# aspirin.net
KiCad netlist of a schematic drawn in EAGLE
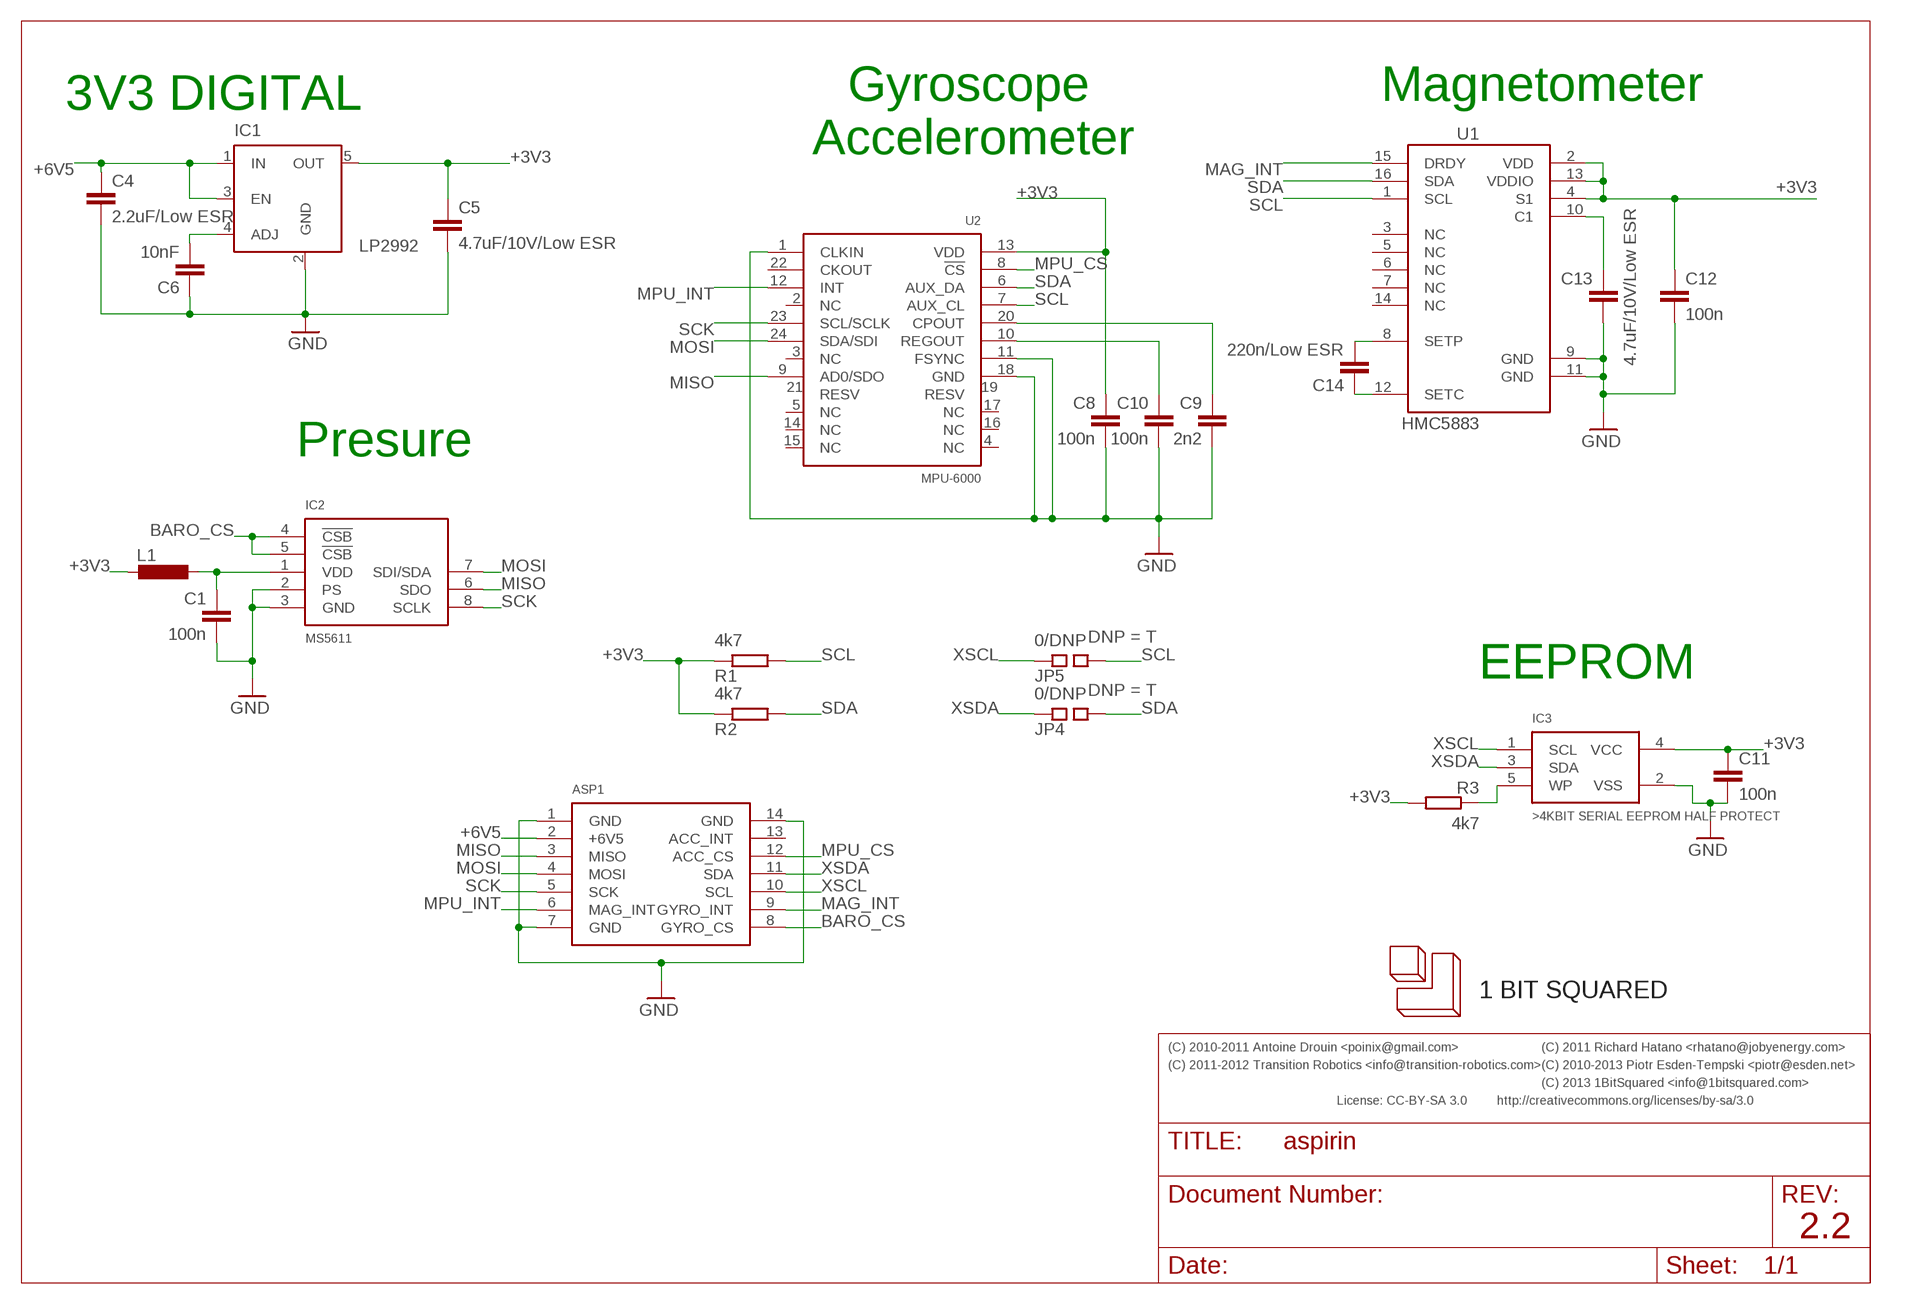
[diagram p0: schematic, sheet 1]

(export (version "E")
  (design (tool "Eeschema 10.0.6"))
  (components
    (comp (ref "ASP1")
      (value "ASPIRIN")
      (footprint "eagle-import:ASPIRIN_CASTELLATED")
      (fields (field (name "PARTNO") "pcb-aspirin"))
      (libsource (lib "eagle-import") (part "ASPIRIN"))
    )
    (comp (ref "C1")
      (value "100n")
      (footprint "eagle-import:0402-CAP")
      (fields (field (name "PARTNO") "cap-cer-0402-100n"))
      (libsource (lib "eagle-import") (part "CAPACITOR-0402"))
    )
    (comp (ref "C4")
      (value "2.2uF/Low ESR")
      (footprint "eagle-import:0603-CAP")
      (fields (field (name "PARTNO") "cap-cer-0603-2u2"))
      (libsource (lib "eagle-import") (part "CAPACITOR-0603"))
    )
    (comp (ref "C5")
      (value "4.7uF/10V/Low ESR")
      (footprint "eagle-import:0603-CAP")
      (fields (field (name "PARTNO") "cap-cer-0603-4u7"))
      (libsource (lib "eagle-import") (part "CAPACITOR-0603"))
    )
    (comp (ref "C6")
      (value "10nF")
      (footprint "eagle-import:0402-CAP")
      (fields (field (name "PARTNO") "cap-cer-0402-10n"))
      (libsource (lib "eagle-import") (part "CAPACITOR-0402"))
    )
    (comp (ref "C8")
      (value "100n")
      (footprint "eagle-import:0402-CAP")
      (fields (field (name "PARTNO") "cap-cer-0402-100n"))
      (libsource (lib "eagle-import") (part "CAPACITOR-0402"))
    )
    (comp (ref "C9")
      (value "2n2")
      (footprint "eagle-import:0402-CAP")
      (fields (field (name "PARTNO") "cap-cer-0402-2n2"))
      (libsource (lib "eagle-import") (part "CAPACITOR-0402"))
    )
    (comp (ref "C10")
      (value "100n")
      (footprint "eagle-import:0402-CAP")
      (fields (field (name "PARTNO") "cap-cer-0402-100n"))
      (libsource (lib "eagle-import") (part "CAPACITOR-0402"))
    )
    (comp (ref "C11")
      (value "100n")
      (footprint "eagle-import:0402-CAP")
      (fields (field (name "PARTNO") "cap-cer-0402-100n"))
      (libsource (lib "eagle-import") (part "CAPACITOR-0402"))
    )
    (comp (ref "C12")
      (value "100n")
      (footprint "eagle-import:0402-CAP")
      (fields (field (name "PARTNO") "cap-cer-0402-100n"))
      (libsource (lib "eagle-import") (part "CAPACITOR-0402"))
    )
    (comp (ref "C13")
      (value "4.7uF/10V/Low ESR")
      (footprint "eagle-import:0603-CAP")
      (fields (field (name "PARTNO") "cap-cer-0603-4u7"))
      (libsource (lib "eagle-import") (part "CAPACITOR-0603"))
    )
    (comp (ref "C14")
      (value "220n/Low ESR")
      (footprint "eagle-import:0603-CAP")
      (fields (field (name "PARTNO") "cap-cer-0603-220n"))
      (libsource (lib "eagle-import") (part "CAPACITOR-0603"))
    )
    (comp (ref "IC1")
      (value "LP2992")
      (footprint "eagle-import:SOT23-5")
      (fields (field (name "PARTNO") "vreg-sot-23-5-3v3"))
      (libsource (lib "eagle-import") (part "MIC5219BM5"))
    )
    (comp (ref "IC2")
      (value "MS5611")
      (footprint "eagle-import:QFN-MS5611")
      (fields (field (name "PARTNO") "sensr-qfn-8-baro"))
      (libsource (lib "eagle-import") (part "MS5611"))
    )
    (comp (ref "IC3")
      (value ">4KBIT SERIAL EEPROM HALF PROTECT")
      (footprint "eagle-import:SOT23-5")
      (fields (field (name "PARTNO") "ic-sot-23-5-4k-eeprom"))
      (libsource (lib "eagle-import") (part "I2C_EEPROM-SOT23-5"))
    )
    (comp (ref "JP4")
      (value "0/DNP")
      (footprint "eagle-import:0402-SQJMP")
      (fields (field (name "DNP") "T") (field (name "PARTNO") "res-0402-0"))
      (libsource (lib "eagle-import") (part "SQ_JMP-0402"))
    )
    (comp (ref "JP5")
      (value "0/DNP")
      (footprint "eagle-import:0402-SQJMP")
      (fields (field (name "DNP") "T") (field (name "PARTNO") "res-0402-0"))
      (libsource (lib "eagle-import") (part "SQ_JMP-0402"))
    )
    (comp (ref "L1")
      (value "INDUCTOR-0603")
      (footprint "eagle-import:0603-IND")
      (fields (field (name "PARTNO") "ferrite-0603-600ohm"))
      (libsource (lib "eagle-import") (part "INDUCTOR-0603"))
    )
    (comp (ref "R1")
      (value "4k7")
      (footprint "eagle-import:0402-RES")
      (fields (field (name "PARTNO") "res-0402-4k7"))
      (libsource (lib "eagle-import") (part "RESISTOR-0402"))
    )
    (comp (ref "R2")
      (value "4k7")
      (footprint "eagle-import:0402-RES")
      (fields (field (name "PARTNO") "res-0402-4k7"))
      (libsource (lib "eagle-import") (part "RESISTOR-0402"))
    )
    (comp (ref "R3")
      (value "4k7")
      (footprint "eagle-import:0402-RES")
      (fields (field (name "PARTNO") "res-0402-4k7"))
      (libsource (lib "eagle-import") (part "RESISTOR-0402"))
    )
    (comp (ref "U$2")
      (value "1B2-NEW-LOGO-3MM")
      (footprint "eagle-import:1B2-NEW-LOGO-3MM")
      (libsource (lib "eagle-import") (part "1B2-NEW-LOGO-3MM"))
    )
    (comp (ref "U1")
      (value "HMC5883")
      (footprint "eagle-import:PLCC16-HMC5883")
      (fields (field (name "PARTNO") "sensr-plcc-16-mag"))
      (libsource (lib "eagle-import") (part "HMC5883"))
    )
    (comp (ref "U2")
      (value "MPU-6000")
      (footprint "eagle-import:QFN24-NO-PAD")
      (fields (field (name "PARTNO") "sensr-qfn-24-acc-gyro"))
      (libsource (lib "eagle-import") (part "MPU-6000"))
    )
  )
  (nets
    (net (code "1") (name "/+3V3") (class "Default")
      (node (ref "C11") (pin "P$1") (pinfunction "1_P$1") (pintype "passive"))
      (node (ref "C12") (pin "P$1") (pinfunction "1_P$1") (pintype "passive"))
      (node (ref "C5") (pin "P$1") (pinfunction "1_P$1") (pintype "passive"))
      (node (ref "C8") (pin "P$1") (pinfunction "1_P$1") (pintype "passive"))
      (node (ref "IC1") (pin "5") (pinfunction "OUT_5") (pintype "output"))
      (node (ref "IC3") (pin "4") (pinfunction "VCC_4") (pintype "bidirectional"))
      (node (ref "L1") (pin "P$2") (pinfunction "2_P$2") (pintype "passive"))
      (node (ref "R1") (pin "P$1") (pinfunction "1_P$1") (pintype "passive"))
      (node (ref "R2") (pin "P$1") (pinfunction "1_P$1") (pintype "passive"))
      (node (ref "R3") (pin "P$2") (pinfunction "2_P$2") (pintype "passive"))
      (node (ref "U1") (pin "13") (pinfunction "VDDIO_13") (pintype "power_in"))
      (node (ref "U1") (pin "2") (pinfunction "VDD_2") (pintype "power_in"))
      (node (ref "U1") (pin "4") (pinfunction "S1_4") (pintype "power_in"))
      (node (ref "U2") (pin "13") (pinfunction "VDD_13") (pintype "bidirectional"))
    )
    (net (code "2") (name "/+6V5") (class "Default")
      (node (ref "ASP1") (pin "2") (pinfunction "+6V5_2") (pintype "bidirectional"))
      (node (ref "C4") (pin "P$1") (pinfunction "1_P$1") (pintype "passive"))
      (node (ref "IC1") (pin "1") (pinfunction "IN_1") (pintype "input"))
      (node (ref "IC1") (pin "3") (pinfunction "EN_3") (pintype "input"))
    )
    (net (code "3") (name "/BARO_CS") (class "Default")
      (node (ref "ASP1") (pin "8") (pinfunction "GYRO_CS_8") (pintype "bidirectional"))
      (node (ref "IC2") (pin "4") (pinfunction "~{CSB}_4") (pintype "bidirectional"))
      (node (ref "IC2") (pin "5") (pinfunction "~{CSB}_5") (pintype "bidirectional"))
    )
    (net (code "4") (name "/MAG_INT") (class "Default")
      (node (ref "ASP1") (pin "9") (pinfunction "GYRO_INT_9") (pintype "bidirectional"))
      (node (ref "U1") (pin "15") (pinfunction "DRDY_15") (pintype "bidirectional"))
    )
    (net (code "5") (name "/MISO") (class "Default")
      (node (ref "ASP1") (pin "3") (pinfunction "MISO_3") (pintype "bidirectional"))
      (node (ref "IC2") (pin "6") (pinfunction "SDO_6") (pintype "bidirectional"))
      (node (ref "U2") (pin "9") (pinfunction "AD0/SDO_9") (pintype "bidirectional"))
    )
    (net (code "6") (name "/MOSI") (class "Default")
      (node (ref "ASP1") (pin "4") (pinfunction "MOSI_4") (pintype "bidirectional"))
      (node (ref "IC2") (pin "7") (pinfunction "SDI/SDA_7") (pintype "bidirectional"))
      (node (ref "U2") (pin "24") (pinfunction "SDA/SDI_24") (pintype "bidirectional"))
    )
    (net (code "7") (name "/MPU_CS") (class "Default")
      (node (ref "ASP1") (pin "12") (pinfunction "ACC_CS_12") (pintype "bidirectional"))
      (node (ref "U2") (pin "8") (pinfunction "~{CS}_8") (pintype "bidirectional"))
    )
    (net (code "8") (name "/MPU_INT") (class "Default")
      (node (ref "ASP1") (pin "6") (pinfunction "MAG_INT_6") (pintype "bidirectional"))
      (node (ref "U2") (pin "12") (pinfunction "INT_12") (pintype "bidirectional"))
    )
    (net (code "9") (name "/SCK") (class "Default")
      (node (ref "ASP1") (pin "5") (pinfunction "SCK_5") (pintype "bidirectional"))
      (node (ref "IC2") (pin "8") (pinfunction "SCLK_8") (pintype "bidirectional"))
      (node (ref "U2") (pin "23") (pinfunction "SCL/SCLK_23") (pintype "bidirectional"))
    )
    (net (code "10") (name "/SCL") (class "Default")
      (node (ref "JP5") (pin "P$2") (pinfunction "2_P$2") (pintype "passive"))
      (node (ref "R1") (pin "P$2") (pinfunction "2_P$2") (pintype "passive"))
      (node (ref "U1") (pin "1") (pinfunction "SCL_1") (pintype "bidirectional"))
      (node (ref "U2") (pin "7") (pinfunction "AUX_CL_7") (pintype "bidirectional"))
    )
    (net (code "11") (name "/SDA") (class "Default")
      (node (ref "JP4") (pin "P$2") (pinfunction "2_P$2") (pintype "passive"))
      (node (ref "R2") (pin "P$2") (pinfunction "2_P$2") (pintype "passive"))
      (node (ref "U1") (pin "16") (pinfunction "SDA_16") (pintype "bidirectional"))
      (node (ref "U2") (pin "6") (pinfunction "AUX_DA_6") (pintype "bidirectional"))
    )
    (net (code "12") (name "/XSCL") (class "Default")
      (node (ref "ASP1") (pin "10") (pinfunction "SCL_10") (pintype "bidirectional"))
      (node (ref "IC3") (pin "1") (pinfunction "SCL_1") (pintype "bidirectional"))
      (node (ref "JP5") (pin "P$1") (pinfunction "1_P$1") (pintype "passive"))
    )
    (net (code "13") (name "/XSDA") (class "Default")
      (node (ref "ASP1") (pin "11") (pinfunction "SDA_11") (pintype "bidirectional"))
      (node (ref "IC3") (pin "3") (pinfunction "SDA_3") (pintype "bidirectional"))
      (node (ref "JP4") (pin "P$1") (pinfunction "1_P$1") (pintype "passive"))
    )
    (net (code "14") (name "GND") (class "Default")
      (node (ref "ASP1") (pin "1") (pinfunction "GND_1") (pintype "bidirectional"))
      (node (ref "ASP1") (pin "14") (pinfunction "GND_14") (pintype "bidirectional"))
      (node (ref "ASP1") (pin "7") (pinfunction "GND_7") (pintype "bidirectional"))
      (node (ref "C1") (pin "P$2") (pinfunction "2_P$2") (pintype "passive"))
      (node (ref "C10") (pin "P$2") (pinfunction "2_P$2") (pintype "passive"))
      (node (ref "C11") (pin "P$2") (pinfunction "2_P$2") (pintype "passive"))
      (node (ref "C12") (pin "P$2") (pinfunction "2_P$2") (pintype "passive"))
      (node (ref "C13") (pin "P$2") (pinfunction "2_P$2") (pintype "passive"))
      (node (ref "C4") (pin "P$2") (pinfunction "2_P$2") (pintype "passive"))
      (node (ref "C5") (pin "P$2") (pinfunction "2_P$2") (pintype "passive"))
      (node (ref "C6") (pin "P$1") (pinfunction "1_P$1") (pintype "passive"))
      (node (ref "C8") (pin "P$2") (pinfunction "2_P$2") (pintype "passive"))
      (node (ref "C9") (pin "P$2") (pinfunction "2_P$2") (pintype "passive"))
      (node (ref "IC1") (pin "2") (pinfunction "GND_2") (pintype "power_in"))
      (node (ref "IC2") (pin "2") (pinfunction "PS_2") (pintype "bidirectional"))
      (node (ref "IC2") (pin "3") (pinfunction "GND_3") (pintype "bidirectional"))
      (node (ref "IC3") (pin "2") (pinfunction "VSS_2") (pintype "bidirectional"))
      (node (ref "U1") (pin "11") (pinfunction "GND_11") (pintype "power_in"))
      (node (ref "U1") (pin "9") (pinfunction "GND_9") (pintype "power_in"))
      (node (ref "U2") (pin "1") (pinfunction "CLKIN_1") (pintype "bidirectional"))
      (node (ref "U2") (pin "11") (pinfunction "FSYNC_11") (pintype "bidirectional"))
      (node (ref "U2") (pin "18") (pinfunction "GND_18") (pintype "bidirectional"))
    )
    (net (code "15") (name "Net-(C1-1)") (class "Default")
      (node (ref "C1") (pin "P$1") (pinfunction "1_P$1") (pintype "passive"))
      (node (ref "IC2") (pin "1") (pinfunction "VDD_1") (pintype "bidirectional"))
      (node (ref "L1") (pin "P$1") (pinfunction "1_P$1") (pintype "passive"))
    )
    (net (code "16") (name "Net-(C6-2)") (class "Default")
      (node (ref "C6") (pin "P$2") (pinfunction "2_P$2") (pintype "passive"))
      (node (ref "IC1") (pin "4") (pinfunction "ADJ_4") (pintype "passive"))
    )
    (net (code "17") (name "Net-(C9-1)") (class "Default")
      (node (ref "C9") (pin "P$1") (pinfunction "1_P$1") (pintype "passive"))
      (node (ref "U2") (pin "20") (pinfunction "CPOUT_20") (pintype "bidirectional"))
    )
    (net (code "18") (name "Net-(C10-1)") (class "Default")
      (node (ref "C10") (pin "P$1") (pinfunction "1_P$1") (pintype "passive"))
      (node (ref "U2") (pin "10") (pinfunction "REGOUT_10") (pintype "bidirectional"))
    )
    (net (code "19") (name "Net-(C13-1)") (class "Default")
      (node (ref "C13") (pin "P$1") (pinfunction "1_P$1") (pintype "passive"))
      (node (ref "U1") (pin "10") (pinfunction "C1_10") (pintype "bidirectional"))
    )
    (net (code "20") (name "Net-(C14-1)") (class "Default")
      (node (ref "C14") (pin "P$1") (pinfunction "1_P$1") (pintype "passive"))
      (node (ref "U1") (pin "12") (pinfunction "SETC_12") (pintype "bidirectional"))
    )
    (net (code "21") (name "Net-(C14-2)") (class "Default")
      (node (ref "C14") (pin "P$2") (pinfunction "2_P$2") (pintype "passive"))
      (node (ref "U1") (pin "8") (pinfunction "SETP_8") (pintype "bidirectional"))
    )
    (net (code "22") (name "Net-(IC3-WP)") (class "Default")
      (node (ref "IC3") (pin "5") (pinfunction "WP_5") (pintype "bidirectional"))
      (node (ref "R3") (pin "P$1") (pinfunction "1_P$1") (pintype "passive"))
    )
    (net (code "23") (name "unconnected-(ASP1-ACC_INT-Pad13)") (class "Default")
      (node (ref "ASP1") (pin "13") (pinfunction "ACC_INT_13") (pintype "bidirectional"))
    )
    (net (code "24") (name "unconnected-(U1-NC-Pad3)") (class "Default")
      (node (ref "U1") (pin "3") (pinfunction "NC_3") (pintype "no_connect"))
    )
    (net (code "25") (name "unconnected-(U1-NC-Pad5)") (class "Default")
      (node (ref "U1") (pin "5") (pinfunction "NC_5") (pintype "no_connect"))
    )
    (net (code "26") (name "unconnected-(U1-NC-Pad6)") (class "Default")
      (node (ref "U1") (pin "6") (pinfunction "NC_6") (pintype "no_connect"))
    )
    (net (code "27") (name "unconnected-(U1-NC-Pad7)") (class "Default")
      (node (ref "U1") (pin "7") (pinfunction "NC_7") (pintype "no_connect"))
    )
    (net (code "28") (name "unconnected-(U1-NC-Pad14)") (class "Default")
      (node (ref "U1") (pin "14") (pinfunction "NC_14") (pintype "no_connect"))
    )
    (net (code "29") (name "unconnected-(U2-CKOUT-Pad22)") (class "Default")
      (node (ref "U2") (pin "22") (pinfunction "CKOUT_22") (pintype "bidirectional"))
    )
    (net (code "30") (name "unconnected-(U2-NC-Pad2)") (class "Default")
      (node (ref "U2") (pin "2") (pinfunction "NC_2") (pintype "bidirectional"))
    )
    (net (code "31") (name "unconnected-(U2-NC-Pad3)") (class "Default")
      (node (ref "U2") (pin "3") (pinfunction "NC_3") (pintype "bidirectional"))
    )
    (net (code "32") (name "unconnected-(U2-NC-Pad4)") (class "Default")
      (node (ref "U2") (pin "4") (pinfunction "NC_4") (pintype "bidirectional"))
    )
    (net (code "33") (name "unconnected-(U2-NC-Pad5)") (class "Default")
      (node (ref "U2") (pin "5") (pinfunction "NC_5") (pintype "bidirectional"))
    )
    (net (code "34") (name "unconnected-(U2-NC-Pad14)") (class "Default")
      (node (ref "U2") (pin "14") (pinfunction "NC_14") (pintype "bidirectional"))
    )
    (net (code "35") (name "unconnected-(U2-NC-Pad15)") (class "Default")
      (node (ref "U2") (pin "15") (pinfunction "NC_15") (pintype "bidirectional"))
    )
    (net (code "36") (name "unconnected-(U2-NC-Pad16)") (class "Default")
      (node (ref "U2") (pin "16") (pinfunction "NC_16") (pintype "bidirectional"))
    )
    (net (code "37") (name "unconnected-(U2-NC-Pad17)") (class "Default")
      (node (ref "U2") (pin "17") (pinfunction "NC_17") (pintype "bidirectional"))
    )
    (net (code "38") (name "unconnected-(U2-RESV-Pad19)") (class "Default")
      (node (ref "U2") (pin "19") (pinfunction "RESV_19") (pintype "bidirectional"))
    )
    (net (code "39") (name "unconnected-(U2-RESV-Pad21)") (class "Default")
      (node (ref "U2") (pin "21") (pinfunction "RESV_21") (pintype "bidirectional"))
    )
  )
)
